# control.net
KiCad netlist of a schematic drawn in Altium Designer
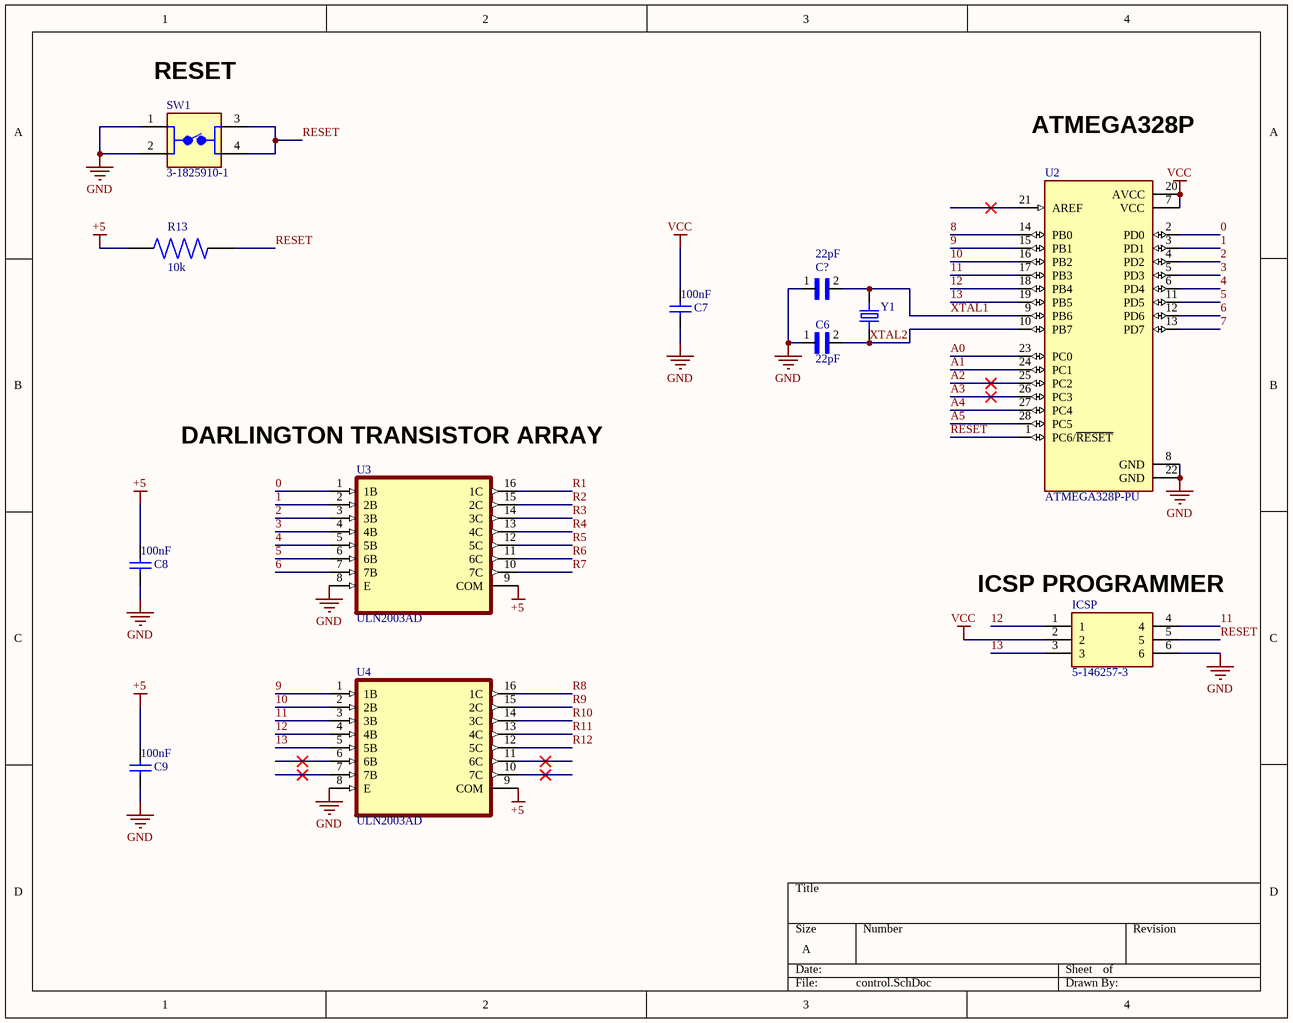
[diagram p0: control.SchDoc]

(export (version "E")
  (design (tool "Eeschema 10.0.6"))
  (components
    (comp (ref "C5")
      (value "22pF")
      (footprint "control:CAPC2012X130N")
      (description "Cap Cer 22pf 50v C0g/Np0 0805")
      (fields
        (field (name "ALTIUM_VALUE") "C?")
        (field (name "MF") "Syfer")
        (field (name "MP") "0805Y0500220JCT")
      )
      (libsource (lib "control") (part "0805Y0500220JCT"))
    )
    (comp (ref "C6")
      (value "22pF")
      (footprint "control:CAPC2012X130N")
      (description "Cap Cer 22pf 50v C0g/Np0 0805")
      (fields (field (name "MF") "Syfer") (field (name "MP") "0805Y0500220JCT"))
      (libsource (lib "control") (part "0805Y0500220JCT"))
    )
    (comp (ref "C7")
      (value "100nF")
      (footprint "WCAP-CSGP_0603_L1.6W0.8H0.8_Wave")
      (description "WCAP-CSGP Multilayer Ceramic Chip Capacitor, General Purpose, size 0603, X7R, 100nF, 25VDC")
      (fields
        (field (name "MANUFACTURER PART NUMBER") "885012206071")
        (field (name "MANUFACTURER") "Wurth Elektronik")
      )
      (libsource (lib "input") (part "885012206071"))
    )
    (comp (ref "C8")
      (value "100nF")
      (footprint "WCAP-CSGP_0603_L1.6W0.8H0.8_Wave")
      (description "WCAP-CSGP Multilayer Ceramic Chip Capacitor, General Purpose, size 0603, X7R, 100nF, 25VDC")
      (fields
        (field (name "MANUFACTURER PART NUMBER") "885012206071")
        (field (name "MANUFACTURER") "Wurth Elektronik")
      )
      (libsource (lib "input") (part "885012206071"))
    )
    (comp (ref "C9")
      (value "100nF")
      (footprint "WCAP-CSGP_0603_L1.6W0.8H0.8_Wave")
      (description "WCAP-CSGP Multilayer Ceramic Chip Capacitor, General Purpose, size 0603, X7R, 100nF, 25VDC")
      (fields
        (field (name "MANUFACTURER PART NUMBER") "885012206071")
        (field (name "MANUFACTURER") "Wurth Elektronik")
      )
      (libsource (lib "input") (part "885012206071"))
    )
    (comp (ref "ICSP")
      (value "5-146257-3")
      (footprint "TE_5-146257-3")
      (description "Header; Breakaway; 0.100 x 0.100 in.; PC Board; Dual; 6; 0.025 in.; 0.12 in.")
      (fields (field (name "MF") "TE Connectivity"))
      (libsource (lib "control") (part "5-146257-3"))
    )
    (comp (ref "R13")
      (value "10k")
      (footprint "RESC3216X70N")
      (description "Res 1206 10 Ohm 5% 1/8W Â±500ppm/Â°C Molded SMD SMD T/R")
      (fields (field (name "TOLERANCE") "5%") (field (name "MP") "FCR1206J10R"))
      (libsource (lib "input") (part "FCR1206J10R"))
    )
    (comp (ref "SW1")
      (value "3-1825910-1")
      (footprint "TE_3-1825910-1")
      (description "Switch Push Button OFF (ON) SPST Round Button 0.05A 24VDC Momentary Contact PC Pins Thru-Hole")
      (fields (field (name "MF") "TE Connectivity"))
      (libsource (lib "control") (part "3-1825910-1"))
    )
    (comp (ref "U2")
      (value "ATMEGA328P-PU")
      (footprint "DIL28")
      (description "ATmega Series 20 MHz 32 KB Flash 2 KB SRAM 8-Bit Microcontroller - DIP-28")
      (libsource (lib "control") (part "ATMEGA328P-PU"))
    )
    (comp (ref "U3")
      (value "ULN2003AD")
      (footprint "SOIC127P600X175-16N")
      (description "50-V, 7-ch darlington transistor array, -20C to 70C")
      (fields (field (name "MF") "Texas Instruments"))
      (libsource (lib "control") (part "ULN2003AD"))
    )
    (comp (ref "U4")
      (value "ULN2003AD")
      (footprint "SOIC127P600X175-16N")
      (description "50-V, 7-ch darlington transistor array, -20C to 70C")
      (fields (field (name "MF") "Texas Instruments"))
      (libsource (lib "control") (part "ULN2003AD"))
    )
    (comp (ref "Y1")
      (value "~")
      (footprint "control:XTAL_ECS-160-20-3X-TR")
      (description "16MHz Â±30ppm Crystal 20pF 50 Ohms HC-49/US")
      (fields (field (name "DIGI-KEY_PART_NUMBER") "XC1776CT-ND") (field (name "MP") "ECS-160-20-3X-TR"))
      (libsource (lib "control") (part "ECS-160-20-3X-TR"))
    )
  )
  (nets
    (net (code "1") (name "+5") (class "Default")
      (node (ref "C8") (pin "2") (pinfunction "2_2") (pintype "passive"))
      (node (ref "C9") (pin "2") (pinfunction "2_2") (pintype "passive"))
      (node (ref "R13") (pin "1") (pinfunction "1_1") (pintype "passive"))
      (node (ref "U3") (pin "9") (pinfunction "COM_9") (pintype "power_in"))
      (node (ref "U4") (pin "9") (pinfunction "COM_9") (pintype "power_in"))
    )
    (net (code "2") (name "/0") (class "Default")
      (node (ref "U2") (pin "2") (pinfunction "PD0_2") (pintype "bidirectional"))
      (node (ref "U3") (pin "1") (pinfunction "1B_1") (pintype "input"))
    )
    (net (code "3") (name "/1") (class "Default")
      (node (ref "U2") (pin "3") (pinfunction "PD1_3") (pintype "bidirectional"))
      (node (ref "U3") (pin "2") (pinfunction "2B_2") (pintype "input"))
    )
    (net (code "4") (name "/2") (class "Default")
      (node (ref "U2") (pin "4") (pinfunction "PD2_4") (pintype "bidirectional"))
      (node (ref "U3") (pin "3") (pinfunction "3B_3") (pintype "input"))
    )
    (net (code "5") (name "/3") (class "Default")
      (node (ref "U2") (pin "5") (pinfunction "PD3_5") (pintype "bidirectional"))
      (node (ref "U3") (pin "4") (pinfunction "4B_4") (pintype "input"))
    )
    (net (code "6") (name "/4") (class "Default")
      (node (ref "U2") (pin "6") (pinfunction "PD4_6") (pintype "bidirectional"))
      (node (ref "U3") (pin "5") (pinfunction "5B_5") (pintype "input"))
    )
    (net (code "7") (name "/5") (class "Default")
      (node (ref "U2") (pin "11") (pinfunction "PD5_11") (pintype "bidirectional"))
      (node (ref "U3") (pin "6") (pinfunction "6B_6") (pintype "input"))
    )
    (net (code "8") (name "/6") (class "Default")
      (node (ref "U2") (pin "12") (pinfunction "PD6_12") (pintype "bidirectional"))
      (node (ref "U3") (pin "7") (pinfunction "7B_7") (pintype "input"))
    )
    (net (code "9") (name "/7") (class "Default")
      (node (ref "U2") (pin "13") (pinfunction "PD7_13") (pintype "bidirectional"))
    )
    (net (code "10") (name "/8") (class "Default")
      (node (ref "U2") (pin "14") (pinfunction "PB0_14") (pintype "bidirectional"))
    )
    (net (code "11") (name "/9") (class "Default")
      (node (ref "U2") (pin "15") (pinfunction "PB1_15") (pintype "bidirectional"))
      (node (ref "U4") (pin "1") (pinfunction "1B_1") (pintype "input"))
    )
    (net (code "12") (name "/10") (class "Default")
      (node (ref "U2") (pin "16") (pinfunction "PB2_16") (pintype "bidirectional"))
      (node (ref "U4") (pin "2") (pinfunction "2B_2") (pintype "input"))
    )
    (net (code "13") (name "/11") (class "Default")
      (node (ref "ICSP") (pin "4") (pinfunction "4_4") (pintype "passive"))
      (node (ref "U2") (pin "17") (pinfunction "PB3_17") (pintype "bidirectional"))
      (node (ref "U4") (pin "3") (pinfunction "3B_3") (pintype "input"))
    )
    (net (code "14") (name "/12") (class "Default")
      (node (ref "ICSP") (pin "1") (pinfunction "1_1") (pintype "passive"))
      (node (ref "U2") (pin "18") (pinfunction "PB4_18") (pintype "bidirectional"))
      (node (ref "U4") (pin "4") (pinfunction "4B_4") (pintype "input"))
    )
    (net (code "15") (name "/13") (class "Default")
      (node (ref "ICSP") (pin "3") (pinfunction "3_3") (pintype "passive"))
      (node (ref "U2") (pin "19") (pinfunction "PB5_19") (pintype "bidirectional"))
      (node (ref "U4") (pin "5") (pinfunction "5B_5") (pintype "input"))
    )
    (net (code "16") (name "/A0") (class "Default")
      (node (ref "U2") (pin "23") (pinfunction "PC0_23") (pintype "bidirectional"))
    )
    (net (code "17") (name "/A1") (class "Default")
      (node (ref "U2") (pin "24") (pinfunction "PC1_24") (pintype "bidirectional"))
    )
    (net (code "18") (name "/A2") (class "Default")
      (node (ref "U2") (pin "25") (pinfunction "PC2_25") (pintype "bidirectional"))
    )
    (net (code "19") (name "/A3") (class "Default")
      (node (ref "U2") (pin "26") (pinfunction "PC3_26") (pintype "bidirectional"))
    )
    (net (code "20") (name "/A4") (class "Default")
      (node (ref "U2") (pin "27") (pinfunction "PC4_27") (pintype "bidirectional"))
    )
    (net (code "21") (name "/A5") (class "Default")
      (node (ref "U2") (pin "28") (pinfunction "PC5_28") (pintype "bidirectional"))
    )
    (net (code "22") (name "/R1") (class "Default")
      (node (ref "U3") (pin "16") (pinfunction "1C_16") (pintype "output"))
    )
    (net (code "23") (name "/R2") (class "Default")
      (node (ref "U3") (pin "15") (pinfunction "2C_15") (pintype "output"))
    )
    (net (code "24") (name "/R3") (class "Default")
      (node (ref "U3") (pin "14") (pinfunction "3C_14") (pintype "output"))
    )
    (net (code "25") (name "/R4") (class "Default")
      (node (ref "U3") (pin "13") (pinfunction "4C_13") (pintype "output"))
    )
    (net (code "26") (name "/R5") (class "Default")
      (node (ref "U3") (pin "12") (pinfunction "5C_12") (pintype "output"))
    )
    (net (code "27") (name "/R6") (class "Default")
      (node (ref "U3") (pin "11") (pinfunction "6C_11") (pintype "output"))
    )
    (net (code "28") (name "/R7") (class "Default")
      (node (ref "U3") (pin "10") (pinfunction "7C_10") (pintype "output"))
    )
    (net (code "29") (name "/R8") (class "Default")
      (node (ref "U4") (pin "16") (pinfunction "1C_16") (pintype "output"))
    )
    (net (code "30") (name "/R9") (class "Default")
      (node (ref "U4") (pin "15") (pinfunction "2C_15") (pintype "output"))
    )
    (net (code "31") (name "/R10") (class "Default")
      (node (ref "U4") (pin "14") (pinfunction "3C_14") (pintype "output"))
    )
    (net (code "32") (name "/R11") (class "Default")
      (node (ref "U4") (pin "13") (pinfunction "4C_13") (pintype "output"))
    )
    (net (code "33") (name "/R12") (class "Default")
      (node (ref "U4") (pin "12") (pinfunction "5C_12") (pintype "output"))
    )
    (net (code "34") (name "/RESET") (class "Default")
      (node (ref "ICSP") (pin "5") (pinfunction "5_5") (pintype "passive"))
      (node (ref "R13") (pin "2") (pinfunction "2_2") (pintype "passive"))
      (node (ref "SW1") (pin "3") (pinfunction "3_3") (pintype "passive"))
      (node (ref "SW1") (pin "4") (pinfunction "4_4") (pintype "passive"))
      (node (ref "U2") (pin "1") (pinfunction "PC6/~{RESET}_1") (pintype "bidirectional"))
    )
    (net (code "35") (name "/XTAL1") (class "Default")
      (node (ref "C5") (pin "2") (pinfunction "2_2") (pintype "passive"))
      (node (ref "U2") (pin "9") (pinfunction "PB6_9") (pintype "bidirectional"))
      (node (ref "Y1") (pin "2") (pinfunction "2_2") (pintype "passive"))
    )
    (net (code "36") (name "/XTAL2") (class "Default")
      (node (ref "C6") (pin "2") (pinfunction "2_2") (pintype "passive"))
      (node (ref "U2") (pin "10") (pinfunction "PB7_10") (pintype "bidirectional"))
      (node (ref "Y1") (pin "1") (pinfunction "1_1") (pintype "passive"))
    )
    (net (code "37") (name "GND") (class "Default")
      (node (ref "C5") (pin "1") (pinfunction "1_1") (pintype "passive"))
      (node (ref "C6") (pin "1") (pinfunction "1_1") (pintype "passive"))
      (node (ref "C7") (pin "1") (pinfunction "1_1") (pintype "passive"))
      (node (ref "C8") (pin "1") (pinfunction "1_1") (pintype "passive"))
      (node (ref "C9") (pin "1") (pinfunction "1_1") (pintype "passive"))
      (node (ref "ICSP") (pin "6") (pinfunction "6_6") (pintype "passive"))
      (node (ref "SW1") (pin "1") (pinfunction "1_1") (pintype "passive"))
      (node (ref "SW1") (pin "2") (pinfunction "2_2") (pintype "passive"))
      (node (ref "U2") (pin "22") (pinfunction "GND_22") (pintype "power_in"))
      (node (ref "U2") (pin "8") (pinfunction "GND_8") (pintype "power_in"))
      (node (ref "U3") (pin "8") (pinfunction "E_8") (pintype "input"))
      (node (ref "U4") (pin "8") (pinfunction "E_8") (pintype "input"))
    )
    (net (code "38") (name "VCC") (class "Default")
      (node (ref "C7") (pin "2") (pinfunction "2_2") (pintype "passive"))
      (node (ref "ICSP") (pin "2") (pinfunction "2_2") (pintype "passive"))
      (node (ref "U2") (pin "20") (pinfunction "AVCC_20") (pintype "power_in"))
      (node (ref "U2") (pin "7") (pinfunction "VCC_7") (pintype "power_in"))
    )
    (net (code "39") (name "unconnected-(U2-AREF-Pad21)") (class "Default")
      (node (ref "U2") (pin "21") (pinfunction "AREF_21") (pintype "input"))
    )
    (net (code "40") (name "unconnected-(U4-6B-Pad6)") (class "Default")
      (node (ref "U4") (pin "6") (pinfunction "6B_6") (pintype "input"))
    )
    (net (code "41") (name "unconnected-(U4-6C-Pad11)") (class "Default")
      (node (ref "U4") (pin "11") (pinfunction "6C_11") (pintype "output"))
    )
    (net (code "42") (name "unconnected-(U4-7B-Pad7)") (class "Default")
      (node (ref "U4") (pin "7") (pinfunction "7B_7") (pintype "input"))
    )
    (net (code "43") (name "unconnected-(U4-7C-Pad10)") (class "Default")
      (node (ref "U4") (pin "10") (pinfunction "7C_10") (pintype "output"))
    )
  )
)
